# Adafruit_PCM5122_I2S_DAC.net
KiCad netlist of a schematic drawn in EAGLE
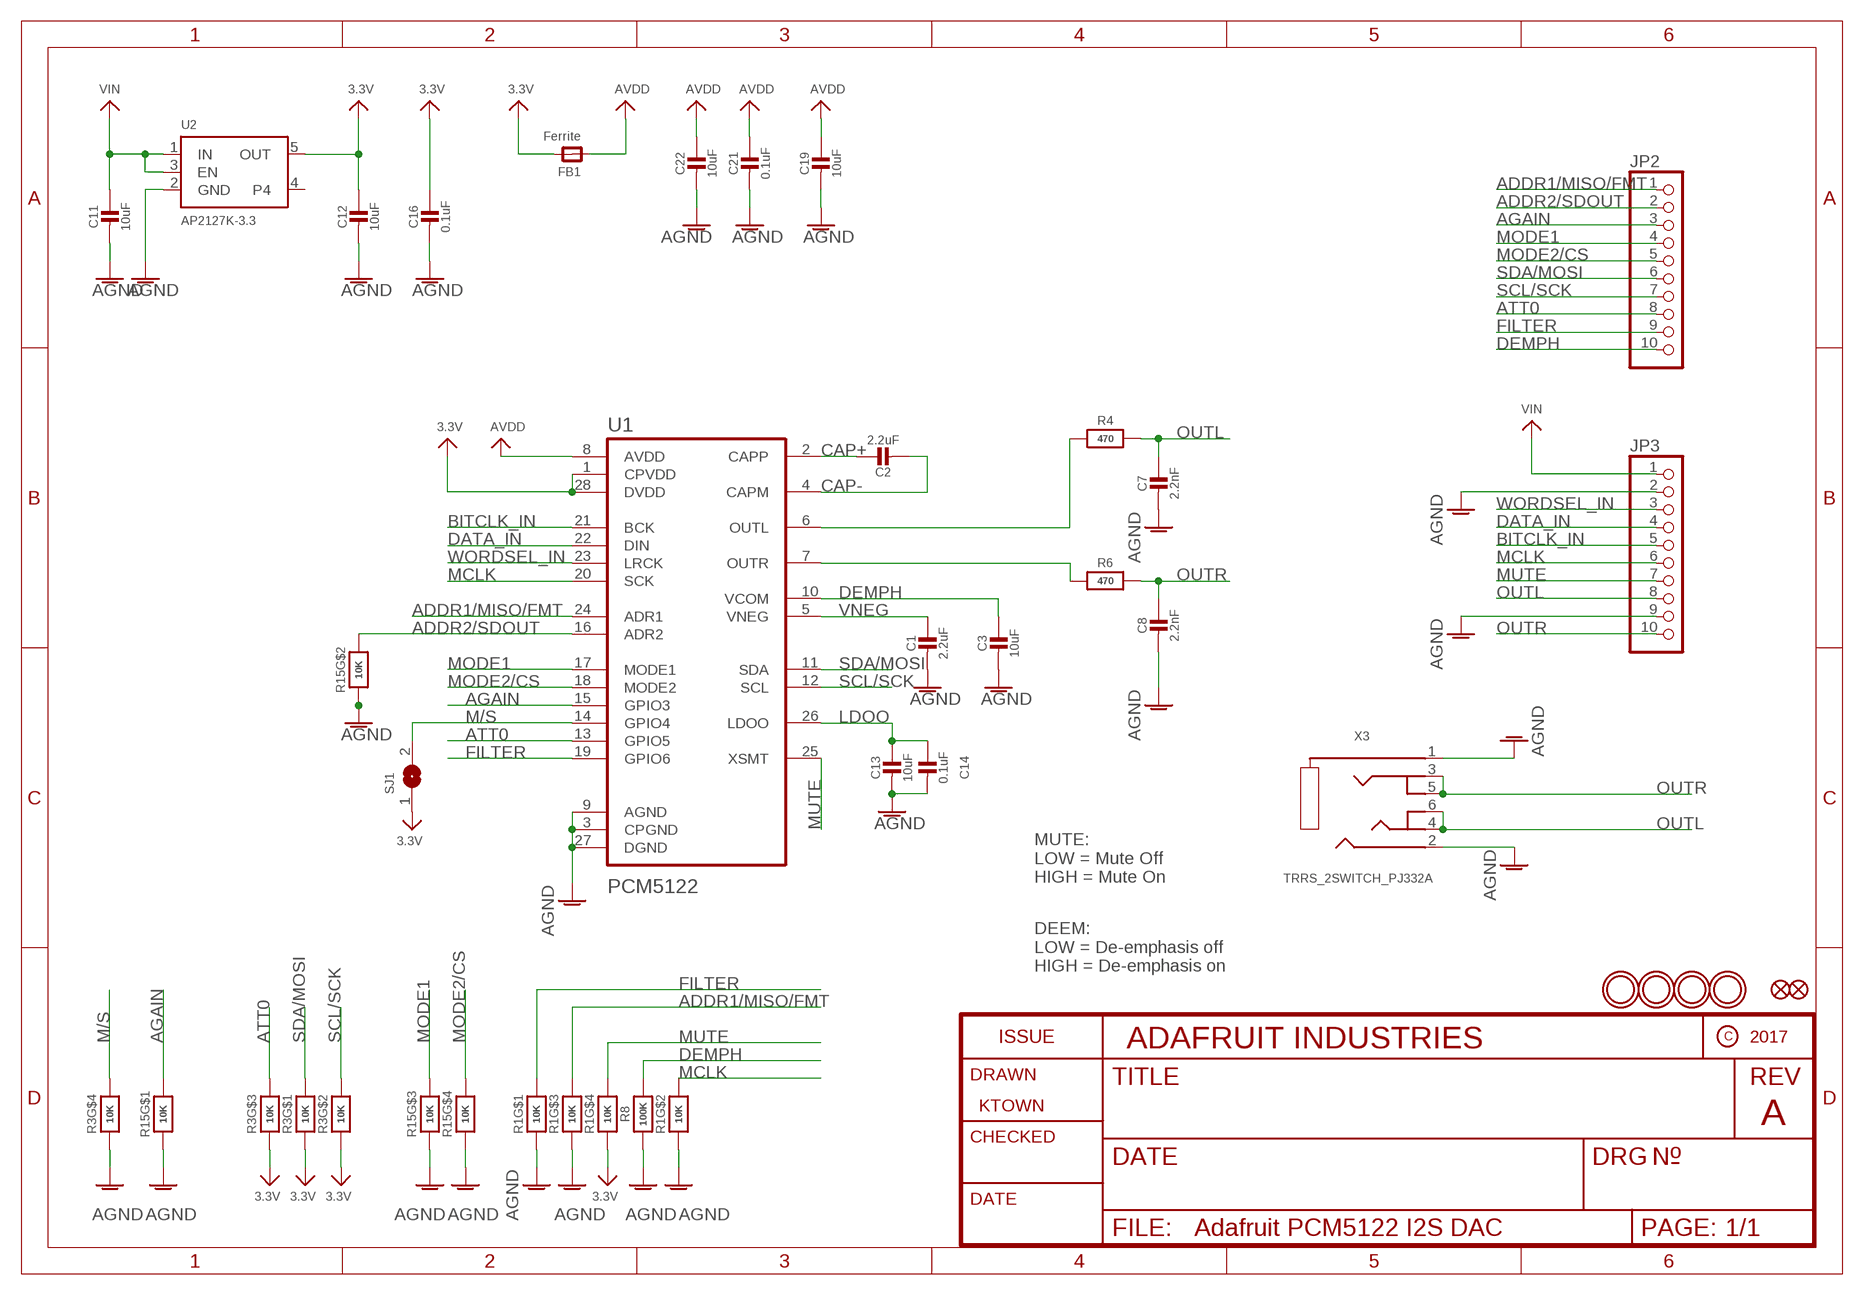
[diagram p0: schematic, sheet 1]

(export (version "E")
  (design (tool "Eeschema 10.0.6"))
  (components
    (comp (ref "C1")
      (value "2.2uF")
      (footprint "eagle-import:0603-NO")
      (libsource (lib "eagle-import") (part "CAP_CERAMIC0603_NO"))
    )
    (comp (ref "C2")
      (value "2.2uF")
      (footprint "eagle-import:0603-NO")
      (libsource (lib "eagle-import") (part "CAP_CERAMIC0603_NO"))
    )
    (comp (ref "C3")
      (value "10uF")
      (footprint "eagle-import:0805-NO")
      (libsource (lib "eagle-import") (part "CAP_CERAMIC0805-NOOUTLINE"))
    )
    (comp (ref "C7")
      (value "2.2nF")
      (footprint "eagle-import:0603-NO")
      (libsource (lib "eagle-import") (part "CAP_CERAMIC0603_NO"))
    )
    (comp (ref "C8")
      (value "2.2nF")
      (footprint "eagle-import:0603-NO")
      (libsource (lib "eagle-import") (part "CAP_CERAMIC0603_NO"))
    )
    (comp (ref "C11")
      (value "10uF")
      (footprint "eagle-import:0805-NO")
      (libsource (lib "eagle-import") (part "CAP_CERAMIC0805-NOOUTLINE"))
    )
    (comp (ref "C12")
      (value "10uF")
      (footprint "eagle-import:0805-NO")
      (libsource (lib "eagle-import") (part "CAP_CERAMIC0805-NOOUTLINE"))
    )
    (comp (ref "C13")
      (value "10uF")
      (footprint "eagle-import:0805-NO")
      (libsource (lib "eagle-import") (part "CAP_CERAMIC0805-NOOUTLINE"))
    )
    (comp (ref "C14")
      (value "0.1uF")
      (footprint "eagle-import:0603-NO")
      (libsource (lib "eagle-import") (part "CAP_CERAMIC0603_NO"))
    )
    (comp (ref "C16")
      (value "0.1uF")
      (footprint "eagle-import:0603-NO")
      (libsource (lib "eagle-import") (part "CAP_CERAMIC0603_NO"))
    )
    (comp (ref "C19")
      (value "10uF")
      (footprint "eagle-import:0805-NO")
      (libsource (lib "eagle-import") (part "CAP_CERAMIC0805-NOOUTLINE"))
    )
    (comp (ref "C21")
      (value "0.1uF")
      (footprint "eagle-import:0603-NO")
      (libsource (lib "eagle-import") (part "CAP_CERAMIC0603_NO"))
    )
    (comp (ref "C22")
      (value "10uF")
      (footprint "eagle-import:0805-NO")
      (libsource (lib "eagle-import") (part "CAP_CERAMIC0805-NOOUTLINE"))
    )
    (comp (ref "FB1")
      (value "Ferrite")
      (footprint "eagle-import:0603-NO")
      (libsource (lib "eagle-import") (part "FERRITE-0603NO"))
    )
    (comp (ref "FID1")
      (value "FIDUCIAL_0.5MM")
      (footprint "eagle-import:FIDUCIAL_0.5MM")
      (libsource (lib "eagle-import") (part "FIDUCIAL_0.5MM"))
    )
    (comp (ref "FID2")
      (value "FIDUCIAL_0.5MM")
      (footprint "eagle-import:FIDUCIAL_0.5MM")
      (libsource (lib "eagle-import") (part "FIDUCIAL_0.5MM"))
    )
    (comp (ref "JP2")
      (value "HEADER-1X1070MIL")
      (footprint "eagle-import:1X10_ROUND70")
      (libsource (lib "eagle-import") (part "HEADER-1X1070MIL"))
    )
    (comp (ref "JP3")
      (value "HEADER-1X1070MIL")
      (footprint "eagle-import:1X10_ROUND70")
      (libsource (lib "eagle-import") (part "HEADER-1X1070MIL"))
    )
    (comp (ref "R1")
      (value "10K")
      (footprint "eagle-import:RESPACK_4X0603")
      (libsource (lib "eagle-import") (part "RESISTOR_4PACK"))
    )
    (comp (ref "R3")
      (value "10K")
      (footprint "eagle-import:RESPACK_4X0603")
      (libsource (lib "eagle-import") (part "RESISTOR_4PACK"))
    )
    (comp (ref "R4")
      (value "470")
      (footprint "eagle-import:0603-NO")
      (libsource (lib "eagle-import") (part "RESISTOR_0603_NOOUT"))
    )
    (comp (ref "R6")
      (value "470")
      (footprint "eagle-import:0603-NO")
      (libsource (lib "eagle-import") (part "RESISTOR_0603_NOOUT"))
    )
    (comp (ref "R8")
      (value "100K")
      (footprint "eagle-import:0603-NO")
      (libsource (lib "eagle-import") (part "RESISTOR_0603_NOOUT"))
    )
    (comp (ref "R15")
      (value "10K")
      (footprint "eagle-import:RESPACK_4X0603")
      (libsource (lib "eagle-import") (part "RESISTOR_4PACK"))
    )
    (comp (ref "SJ1")
      (value "SOLDERJUMPER")
      (footprint "eagle-import:SOLDERJUMPER_ARROW_NOPASTE")
      (libsource (lib "eagle-import") (part "SOLDERJUMPER"))
    )
    (comp (ref "U$11")
      (value "MOUNTINGHOLE2.5")
      (footprint "eagle-import:MOUNTINGHOLE_2.5_PLATED")
      (libsource (lib "eagle-import") (part "MOUNTINGHOLE2.5"))
    )
    (comp (ref "U$12")
      (value "MOUNTINGHOLE2.5")
      (footprint "eagle-import:MOUNTINGHOLE_2.5_PLATED")
      (libsource (lib "eagle-import") (part "MOUNTINGHOLE2.5"))
    )
    (comp (ref "U$13")
      (value "MOUNTINGHOLE2.5")
      (footprint "eagle-import:MOUNTINGHOLE_2.5_PLATED")
      (libsource (lib "eagle-import") (part "MOUNTINGHOLE2.5"))
    )
    (comp (ref "U$14")
      (value "MOUNTINGHOLE2.5")
      (footprint "eagle-import:MOUNTINGHOLE_2.5_PLATED")
      (libsource (lib "eagle-import") (part "MOUNTINGHOLE2.5"))
    )
    (comp (ref "U1")
      (value "PCM5122")
      (footprint "eagle-import:SSOP-28N")
      (libsource (lib "eagle-import") (part "PCM5122"))
    )
    (comp (ref "U2")
      (value "AP2127K-3.3")
      (footprint "eagle-import:SOT23-5")
      (libsource (lib "eagle-import") (part "VREG_SOT23-5"))
    )
    (comp (ref "X3")
      (value "TRRS_2SWITCH_PJ332A")
      (footprint "eagle-import:PJ-332A")
      (libsource (lib "eagle-import") (part "TRRS_2SWITCH_PJ332A"))
    )
  )
  (nets
    (net (code "1") (name "/ADDR1{slash}MISO{slash}FMT") (class "Default")
      (node (ref "JP2") (pin "1") (pinfunction "1_1") (pintype "passive"))
      (node (ref "R1") (pin "6") (pinfunction "2_6") (pintype "passive"))
      (node (ref "U1") (pin "24") (pinfunction "ADR1_24") (pintype "bidirectional"))
    )
    (net (code "2") (name "/ADDR2{slash}SDOUT") (class "Default")
      (node (ref "JP2") (pin "2") (pinfunction "2_2") (pintype "passive"))
      (node (ref "R15") (pin "7") (pinfunction "2_7") (pintype "passive"))
      (node (ref "U1") (pin "16") (pinfunction "ADR2_16") (pintype "bidirectional"))
    )
    (net (code "3") (name "/AGAIN") (class "Default")
      (node (ref "JP2") (pin "3") (pinfunction "3_3") (pintype "passive"))
      (node (ref "R15") (pin "8") (pinfunction "2_8") (pintype "passive"))
      (node (ref "U1") (pin "15") (pinfunction "GPIO3_15") (pintype "bidirectional"))
    )
    (net (code "4") (name "/ATT0") (class "Default")
      (node (ref "JP2") (pin "8") (pinfunction "8_8") (pintype "passive"))
      (node (ref "R3") (pin "6") (pinfunction "2_6") (pintype "passive"))
      (node (ref "U1") (pin "13") (pinfunction "GPIO5_13") (pintype "bidirectional"))
    )
    (net (code "5") (name "/BITCLK_IN") (class "Default")
      (node (ref "JP3") (pin "5") (pinfunction "5_5") (pintype "passive"))
      (node (ref "U1") (pin "21") (pinfunction "BCK_21") (pintype "input"))
    )
    (net (code "6") (name "/CAP+") (class "Default")
      (node (ref "C2") (pin "1") (pinfunction "1_1") (pintype "passive"))
      (node (ref "U1") (pin "2") (pinfunction "CAPP_2") (pintype "output"))
    )
    (net (code "7") (name "/CAP-") (class "Default")
      (node (ref "C2") (pin "2") (pinfunction "2_2") (pintype "passive"))
      (node (ref "U1") (pin "4") (pinfunction "CAPM_4") (pintype "output"))
    )
    (net (code "8") (name "/DATA_IN") (class "Default")
      (node (ref "JP3") (pin "4") (pinfunction "4_4") (pintype "passive"))
      (node (ref "U1") (pin "22") (pinfunction "DIN_22") (pintype "input"))
    )
    (net (code "9") (name "/DEMPH") (class "Default")
      (node (ref "C3") (pin "1") (pinfunction "1_1") (pintype "passive"))
      (node (ref "JP2") (pin "10") (pinfunction "10_10") (pintype "passive"))
      (node (ref "R8") (pin "2") (pinfunction "2_2") (pintype "passive"))
      (node (ref "U1") (pin "10") (pinfunction "VCOM_10") (pintype "output"))
    )
    (net (code "10") (name "/FILTER") (class "Default")
      (node (ref "JP2") (pin "9") (pinfunction "9_9") (pintype "passive"))
      (node (ref "R1") (pin "8") (pinfunction "2_8") (pintype "passive"))
      (node (ref "U1") (pin "19") (pinfunction "GPIO6_19") (pintype "bidirectional"))
    )
    (net (code "11") (name "/LDOO") (class "Default")
      (node (ref "C13") (pin "1") (pinfunction "1_1") (pintype "passive"))
      (node (ref "C14") (pin "1") (pinfunction "1_1") (pintype "passive"))
      (node (ref "U1") (pin "26") (pinfunction "LDOO_26") (pintype "bidirectional"))
    )
    (net (code "12") (name "/MCLK") (class "Default")
      (node (ref "JP3") (pin "6") (pinfunction "6_6") (pintype "passive"))
      (node (ref "R1") (pin "7") (pinfunction "2_7") (pintype "passive"))
      (node (ref "U1") (pin "20") (pinfunction "SCK_20") (pintype "input"))
    )
    (net (code "13") (name "/MODE1") (class "Default")
      (node (ref "JP2") (pin "4") (pinfunction "4_4") (pintype "passive"))
      (node (ref "R15") (pin "6") (pinfunction "2_6") (pintype "passive"))
      (node (ref "U1") (pin "17") (pinfunction "MODE1_17") (pintype "input"))
    )
    (net (code "14") (name "/MODE2{slash}CS") (class "Default")
      (node (ref "JP2") (pin "5") (pinfunction "5_5") (pintype "passive"))
      (node (ref "R15") (pin "5") (pinfunction "2_5") (pintype "passive"))
      (node (ref "U1") (pin "18") (pinfunction "MODE2_18") (pintype "input"))
    )
    (net (code "15") (name "/MUTE") (class "Default")
      (node (ref "JP3") (pin "7") (pinfunction "7_7") (pintype "passive"))
      (node (ref "R1") (pin "5") (pinfunction "2_5") (pintype "passive"))
      (node (ref "U1") (pin "25") (pinfunction "XSMT_25") (pintype "input"))
    )
    (net (code "16") (name "/M{slash}S") (class "Default")
      (node (ref "R3") (pin "5") (pinfunction "2_5") (pintype "passive"))
      (node (ref "SJ1") (pin "2") (pinfunction "2_2") (pintype "passive"))
      (node (ref "U1") (pin "14") (pinfunction "GPIO4_14") (pintype "bidirectional"))
    )
    (net (code "17") (name "/OUTL") (class "Default")
      (node (ref "C7") (pin "1") (pinfunction "1_1") (pintype "passive"))
      (node (ref "JP3") (pin "8") (pinfunction "8_8") (pintype "passive"))
      (node (ref "R4") (pin "2") (pinfunction "2_2") (pintype "passive"))
      (node (ref "X3") (pin "4") (pinfunction "TIP_4") (pintype "passive"))
      (node (ref "X3") (pin "6") (pinfunction "TIP_SW_6") (pintype "passive"))
    )
    (net (code "18") (name "/OUTR") (class "Default")
      (node (ref "C8") (pin "1") (pinfunction "1_1") (pintype "passive"))
      (node (ref "JP3") (pin "10") (pinfunction "10_10") (pintype "passive"))
      (node (ref "R6") (pin "2") (pinfunction "2_2") (pintype "passive"))
      (node (ref "X3") (pin "3") (pinfunction "RING2_3") (pintype "passive"))
      (node (ref "X3") (pin "5") (pinfunction "R2_SW_5") (pintype "passive"))
    )
    (net (code "19") (name "/SCL{slash}SCK") (class "Default")
      (node (ref "JP2") (pin "7") (pinfunction "7_7") (pintype "passive"))
      (node (ref "R3") (pin "7") (pinfunction "2_7") (pintype "passive"))
      (node (ref "U1") (pin "12") (pinfunction "SCL_12") (pintype "input"))
    )
    (net (code "20") (name "/SDA{slash}MOSI") (class "Default")
      (node (ref "JP2") (pin "6") (pinfunction "6_6") (pintype "passive"))
      (node (ref "R3") (pin "8") (pinfunction "2_8") (pintype "passive"))
      (node (ref "U1") (pin "11") (pinfunction "SDA_11") (pintype "bidirectional"))
    )
    (net (code "21") (name "/VNEG") (class "Default")
      (node (ref "C1") (pin "1") (pinfunction "1_1") (pintype "passive"))
      (node (ref "U1") (pin "5") (pinfunction "VNEG_5") (pintype "output"))
    )
    (net (code "22") (name "/WORDSEL_IN") (class "Default")
      (node (ref "JP3") (pin "3") (pinfunction "3_3") (pintype "passive"))
      (node (ref "U1") (pin "23") (pinfunction "LRCK_23") (pintype "bidirectional"))
    )
    (net (code "23") (name "3.3V") (class "Default")
      (node (ref "C12") (pin "1") (pinfunction "1_1") (pintype "passive"))
      (node (ref "C16") (pin "1") (pinfunction "1_1") (pintype "passive"))
      (node (ref "FB1") (pin "2") (pinfunction "P$2_2") (pintype "passive"))
      (node (ref "R1") (pin "4") (pinfunction "1_4") (pintype "passive"))
      (node (ref "R3") (pin "1") (pinfunction "1_1") (pintype "passive"))
      (node (ref "R3") (pin "2") (pinfunction "1_2") (pintype "passive"))
      (node (ref "R3") (pin "3") (pinfunction "1_3") (pintype "passive"))
      (node (ref "SJ1") (pin "1") (pinfunction "1_1") (pintype "passive"))
      (node (ref "U1") (pin "1") (pinfunction "CPVDD_1") (pintype "power_in"))
      (node (ref "U1") (pin "28") (pinfunction "DVDD_28") (pintype "power_in"))
      (node (ref "U2") (pin "5") (pinfunction "OUT_5") (pintype "power_in"))
    )
    (net (code "24") (name "AGND") (class "Default")
      (node (ref "C1") (pin "2") (pinfunction "2_2") (pintype "passive"))
      (node (ref "C11") (pin "2") (pinfunction "2_2") (pintype "passive"))
      (node (ref "C12") (pin "2") (pinfunction "2_2") (pintype "passive"))
      (node (ref "C13") (pin "2") (pinfunction "2_2") (pintype "passive"))
      (node (ref "C14") (pin "2") (pinfunction "2_2") (pintype "passive"))
      (node (ref "C16") (pin "2") (pinfunction "2_2") (pintype "passive"))
      (node (ref "C19") (pin "2") (pinfunction "2_2") (pintype "passive"))
      (node (ref "C21") (pin "2") (pinfunction "2_2") (pintype "passive"))
      (node (ref "C22") (pin "2") (pinfunction "2_2") (pintype "passive"))
      (node (ref "C3") (pin "2") (pinfunction "2_2") (pintype "passive"))
      (node (ref "C7") (pin "2") (pinfunction "2_2") (pintype "passive"))
      (node (ref "C8") (pin "2") (pinfunction "2_2") (pintype "passive"))
      (node (ref "JP3") (pin "2") (pinfunction "2_2") (pintype "passive"))
      (node (ref "JP3") (pin "9") (pinfunction "9_9") (pintype "passive"))
      (node (ref "R1") (pin "1") (pinfunction "1_1") (pintype "passive"))
      (node (ref "R1") (pin "2") (pinfunction "1_2") (pintype "passive"))
      (node (ref "R1") (pin "3") (pinfunction "1_3") (pintype "passive"))
      (node (ref "R15") (pin "1") (pinfunction "1_1") (pintype "passive"))
      (node (ref "R15") (pin "2") (pinfunction "1_2") (pintype "passive"))
      (node (ref "R15") (pin "3") (pinfunction "1_3") (pintype "passive"))
      (node (ref "R15") (pin "4") (pinfunction "1_4") (pintype "passive"))
      (node (ref "R3") (pin "4") (pinfunction "1_4") (pintype "passive"))
      (node (ref "R8") (pin "1") (pinfunction "1_1") (pintype "passive"))
      (node (ref "U1") (pin "27") (pinfunction "DGND_27") (pintype "power_in"))
      (node (ref "U1") (pin "3") (pinfunction "CPGND_3") (pintype "power_in"))
      (node (ref "U1") (pin "9") (pinfunction "AGND_9") (pintype "power_in"))
      (node (ref "U2") (pin "2") (pinfunction "GND_2") (pintype "power_in"))
      (node (ref "X3") (pin "1") (pinfunction "RING_1") (pintype "passive"))
      (node (ref "X3") (pin "2") (pinfunction "RING1_2") (pintype "passive"))
    )
    (net (code "25") (name "AVDD") (class "Default")
      (node (ref "C19") (pin "1") (pinfunction "1_1") (pintype "passive"))
      (node (ref "C21") (pin "1") (pinfunction "1_1") (pintype "passive"))
      (node (ref "C22") (pin "1") (pinfunction "1_1") (pintype "passive"))
      (node (ref "FB1") (pin "1") (pinfunction "P$1_1") (pintype "passive"))
      (node (ref "U1") (pin "8") (pinfunction "AVDD_8") (pintype "power_in"))
    )
    (net (code "26") (name "Net-(U1-OUTL)") (class "Default")
      (node (ref "R4") (pin "1") (pinfunction "1_1") (pintype "passive"))
      (node (ref "U1") (pin "6") (pinfunction "OUTL_6") (pintype "output"))
    )
    (net (code "27") (name "Net-(U1-OUTR)") (class "Default")
      (node (ref "R6") (pin "1") (pinfunction "1_1") (pintype "passive"))
      (node (ref "U1") (pin "7") (pinfunction "OUTR_7") (pintype "output"))
    )
    (net (code "28") (name "VIN") (class "Default")
      (node (ref "C11") (pin "1") (pinfunction "1_1") (pintype "passive"))
      (node (ref "JP3") (pin "1") (pinfunction "1_1") (pintype "passive"))
      (node (ref "U2") (pin "1") (pinfunction "IN_1") (pintype "power_in"))
      (node (ref "U2") (pin "3") (pinfunction "EN_3") (pintype "input"))
    )
    (net (code "29") (name "unconnected-(U2-P4-Pad4)") (class "Default")
      (node (ref "U2") (pin "4") (pinfunction "P4_4") (pintype "bidirectional"))
    )
  )
)
